# originalPSU48.net
KiCad netlist of a schematic drawn in Altium Designer
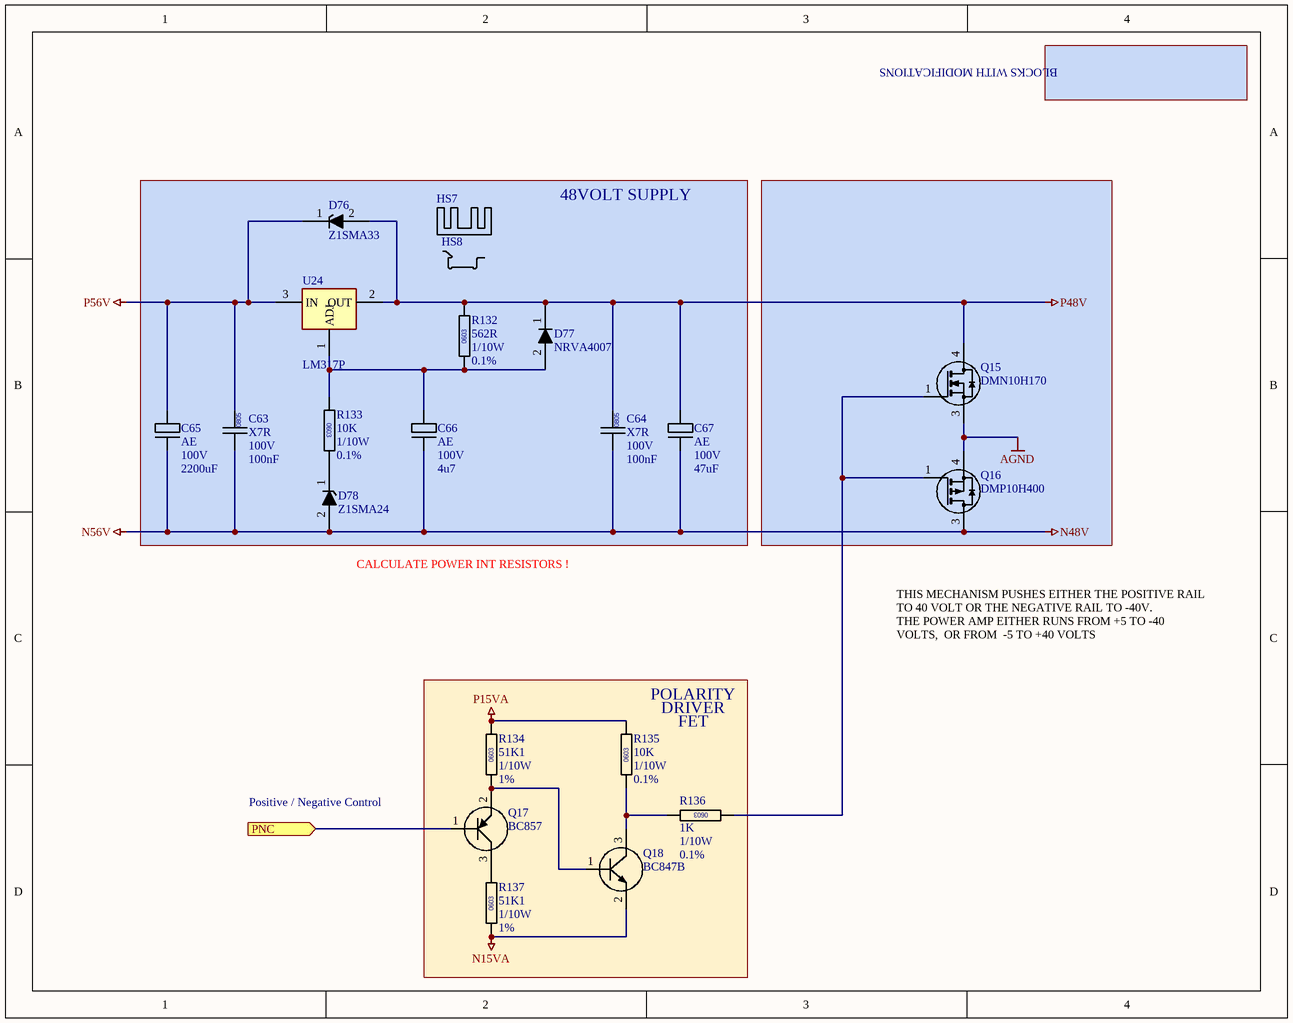
[diagram p0: originalPSU48.SchDoc]

(export (version "E")
  (design (tool "Eeschema 10.0.6"))
  (components
    (comp (ref "C63")
      (value "CAP0805")
      (footprint "CAPC0805")
      (description "CAPACITOR,CERAMIC,100nF,100V,X7R,0805")
      (fields
        (field (name "DIELECTRIC") "X7R")
        (field (name "VOLTAGE") "100V")
        (field (name "CAPACITANCE") "100nF")
      )
      (libsource (lib "CAPACITORS") (part "CAPC-0805-100nF-100V"))
    )
    (comp (ref "C64")
      (value "CAP0805")
      (footprint "CAPC0805")
      (description "CAPACITOR,CERAMIC,100nF,100V,X7R,0805")
      (fields
        (field (name "DIELECTRIC") "X7R")
        (field (name "VOLTAGE") "100V")
        (field (name "CAPACITANCE") "100nF")
      )
      (libsource (lib "CAPACITORS") (part "CAPC-0805-100nF-100V"))
    )
    (comp (ref "C65")
      (value "CAP0603")
      (footprint "CAPAE-NICHICON-LGY2A222MELC30")
      (description "CAPACITOR,ALU,2200uF,100V,TH,P10mm,D35mm,H32mm,SNAP")
      (fields
        (field (name "DIELECTRIC") "AE")
        (field (name "VOLTAGE") "100V")
        (field (name "CAPACITANCE") "2200uF")
      )
      (libsource (lib "CAPACITORS") (part "CAPP-AE-2200uF-100V-TH100P350D320H"))
    )
    (comp (ref "C66")
      (value "CAP0603")
      (footprint "CAPAE-PANASONIC-ECA-2AM4R7I")
      (description "CAPACITOR,ALU,4u7,100V,TH,P0.25mm,D50mm,H12mm")
      (fields
        (field (name "DIELECTRIC") "AE")
        (field (name "VOLTAGE") "100V")
        (field (name "CAPACITANCE") "4u7")
      )
      (libsource (lib "CAPACITORS") (part "CAPP-AE-4u7-100V-TH025P050D120H"))
    )
    (comp (ref "C67")
      (value "CAP0603")
      (footprint "CAPAE-KEMET-ESL476M100AH9AA")
      (description "CAPACITOR,ALU,47uF,100V,TH,P5mm,D10mm,H14mm")
      (fields
        (field (name "DIELECTRIC") "AE")
        (field (name "VOLTAGE") "100V")
        (field (name "CAPACITANCE") "47uF")
      )
      (libsource (lib "CAPACITORS") (part "CAPP-AE-47uF-100V-TH050P100D140H"))
    )
    (comp (ref "D76")
      (value "Z1SMA33")
      (footprint "DO214AC")
      (description "DIODE,ZENER,33V,1W,Z1SMA33,DO214AC(SMA)")
      (libsource (lib "DIODES") (part "ZENER-DIOTEC-Z1SMA33"))
    )
    (comp (ref "D77")
      (value "NRVA4007")
      (footprint "DO214AC")
      (description "DIODE,RECTIFIER,1000V,1A,ONSEMI,NRVA4007,SMA")
      (libsource (lib "DIODES") (part "DIODE-ONSEMI-NRVA4007T3G"))
    )
    (comp (ref "D78")
      (value "Z1SMA24")
      (footprint "DO214AC")
      (description "DIODE,ZENER,24V,1W,Z1SMA24,DO214AC(SMA)")
      (libsource (lib "DIODES") (part "ZENER-DIOTEC-Z1SMA24"))
    )
    (comp (ref "HS7")
      (value "HEATSINK-CUI-HSS06-C20-P32")
      (footprint "HEATSINK-CUI-HSS06-C20-P32")
      (description "HEATSINKSTAMPED,CLIP-ON,BOARDMOUNT,3W,25C/W,CUI,HSS06-C20-P32")
      (libsource (lib "HEATSINK") (part "HEATSINK-CUI-HSS06-C20-P32"))
    )
    (comp (ref "HS8")
      (value "HEATSINK-CUI-HSC-05")
      (footprint "HEATSINK-CUI-HSS06-C20-P32")
      (description "HEATSINK,CLIP FOR HSS01-B20-CP")
      (libsource (lib "HEATSINK") (part "HEATSINK-CUI-HSC-05"))
    )
    (comp (ref "Q15")
      (value "DMN10H170")
      (footprint "DPAK")
      (description "XSTR,NMOS,100V,12A,DMN10H170SK3-13,DPAK")
      (libsource (lib "TRANSISTORS") (part "XSTR-NMOS-DIODES-DMN10H170SK3-13"))
    )
    (comp (ref "Q16")
      (value "DMP10H400")
      (footprint "DPAK")
      (description "XSTR,PMOS,100V,5.6A,DMP10H400SK3-13,DPAK")
      (libsource (lib "TRANSISTORS") (part "XSTR-PMOS-DIODES-DMP10H400SK3-13"))
    )
    (comp (ref "Q17")
      (value "BC857")
      (footprint "SOT23")
      (description "XSTR,PNP,SOT23,BC857,SOT23")
      (libsource (lib "TRANSISTORS") (part "XSTR-PNP-BC857"))
    )
    (comp (ref "Q18")
      (value "BC847B")
      (footprint "SOT23")
      (description "XSTR,NPN,45V,0.1A,,BC847B,SOT23")
      (libsource (lib "TRANSISTORS") (part "XSTR-NPN-BC847"))
    )
    (comp (ref "R132")
      (value "562R")
      (footprint "RESC0603")
      (description "RESISTOR,562R,0.1%,100mW,0603 (1608)")
      (fields
        (field (name "POWER") "1/10W")
        (field (name "TOLERANCE") "0.1%")
        (field (name "Comment") "RESC0603")
      )
      (libsource (lib "RESISTORS") (part "RESC-0603-562R-0.1%-1/10W"))
    )
    (comp (ref "R133")
      (value "10K")
      (footprint "RESC0603")
      (description "RESISTOR,10K,0.1%,100mW,0603 (1608)")
      (fields
        (field (name "POWER") "1/10W")
        (field (name "TOLERANCE") "0.1%")
        (field (name "Comment") "RESC0603")
      )
      (libsource (lib "RESISTORS") (part "RESC-0603-10K-0.1%-1/10W"))
    )
    (comp (ref "R134")
      (value "51K1")
      (footprint "RESC0603")
      (description "RESISTOR,51K1,1%,100mW,0603 (1608)")
      (fields
        (field (name "POWER") "1/10W")
        (field (name "TOLERANCE") "1%")
        (field (name "Comment") "RESC0603")
      )
      (libsource (lib "RESISTORS") (part "RESC-0603-51K1-1%-1/10W"))
    )
    (comp (ref "R135")
      (value "10K")
      (footprint "RESC0603")
      (description "RESISTOR,10K,0.1%,100mW,0603 (1608)")
      (fields
        (field (name "POWER") "1/10W")
        (field (name "TOLERANCE") "0.1%")
        (field (name "Comment") "RESC0603")
      )
      (libsource (lib "RESISTORS") (part "RESC-0603-10K-0.1%-1/10W"))
    )
    (comp (ref "R136")
      (value "1K")
      (footprint "RESC0603")
      (description "RESISTOR,1K,0.1%,100mW,0603 (1608)")
      (fields
        (field (name "POWER") "1/10W")
        (field (name "TOLERANCE") "0.1%")
        (field (name "Comment") "RESC0603")
      )
      (libsource (lib "RESISTORS") (part "RESC-0603-1K-0.1%-1/10W"))
    )
    (comp (ref "R137")
      (value "51K1")
      (footprint "RESC0603")
      (description "RESISTOR,51K1,1%,100mW,0603 (1608)")
      (fields
        (field (name "POWER") "1/10W")
        (field (name "TOLERANCE") "1%")
        (field (name "Comment") "RESC0603")
      )
      (libsource (lib "RESISTORS") (part "RESC-0603-51K1-1%-1/10W"))
    )
    (comp (ref "U24")
      (value "LM317P")
      (footprint "TO220V-OVERMOLD")
      (description "IC,VOLTAGE REG,LIN,POSITIVE,ADJ,LM317P,TO220")
      (libsource (lib "IC-REG") (part "IC-ST-LM317P-TO220FP"))
    )
  )
  (nets
    (net (code "1") (name "/PNC") (class "Default")
      (node (ref "Q17") (pin "1") (pinfunction "B_1") (pintype "passive"))
    )
    (net (code "2") (name "AGND") (class "Default")
      (node (ref "Q15") (pin "3") (pinfunction "S_3") (pintype "passive"))
      (node (ref "Q16") (pin "4") (pinfunction "S_4") (pintype "passive"))
    )
    (net (code "3") (name "N15VA") (class "Default")
      (node (ref "Q18") (pin "2") (pinfunction "E_2") (pintype "passive"))
      (node (ref "R137") (pin "2") (pintype "passive"))
    )
    (net (code "4") (name "N48V") (class "Default")
      (node (ref "C63") (pin "2") (pintype "passive"))
      (node (ref "C64") (pin "2") (pintype "passive"))
      (node (ref "C65") (pin "2") (pintype "passive"))
      (node (ref "C66") (pin "2") (pintype "passive"))
      (node (ref "C67") (pin "2") (pintype "passive"))
      (node (ref "D78") (pin "2") (pinfunction "A_2") (pintype "passive"))
      (node (ref "Q16") (pin "3") (pinfunction "D_3") (pintype "passive"))
    )
    (net (code "5") (name "Net-(D77-A)") (class "Default")
      (node (ref "C66") (pin "1") (pintype "passive"))
      (node (ref "D77") (pin "2") (pinfunction "A_2") (pintype "passive"))
      (node (ref "R132") (pin "2") (pintype "passive"))
      (node (ref "R133") (pin "2") (pintype "passive"))
      (node (ref "U24") (pin "1") (pinfunction "ADJ_1") (pintype "passive"))
    )
    (net (code "6") (name "Net-(D78-K)") (class "Default")
      (node (ref "D78") (pin "1") (pinfunction "K_1") (pintype "passive"))
      (node (ref "R133") (pin "1") (pintype "passive"))
    )
    (net (code "7") (name "Net-(Q15-G1)") (class "Default")
      (node (ref "Q15") (pin "1") (pinfunction "G1_1") (pintype "passive"))
      (node (ref "Q16") (pin "1") (pinfunction "G1_1") (pintype "passive"))
      (node (ref "R136") (pin "2") (pintype "passive"))
    )
    (net (code "8") (name "Net-(Q17-C)") (class "Default")
      (node (ref "Q17") (pin "3") (pinfunction "C_3") (pintype "passive"))
      (node (ref "R137") (pin "1") (pintype "passive"))
    )
    (net (code "9") (name "Net-(Q17-E)") (class "Default")
      (node (ref "Q17") (pin "2") (pinfunction "E_2") (pintype "passive"))
      (node (ref "Q18") (pin "1") (pinfunction "B_1") (pintype "passive"))
      (node (ref "R134") (pin "2") (pintype "passive"))
    )
    (net (code "10") (name "Net-(Q18-C)") (class "Default")
      (node (ref "Q18") (pin "3") (pinfunction "C_3") (pintype "passive"))
      (node (ref "R135") (pin "2") (pintype "passive"))
      (node (ref "R136") (pin "1") (pintype "passive"))
    )
    (net (code "11") (name "P15VA") (class "Default")
      (node (ref "R134") (pin "1") (pintype "passive"))
      (node (ref "R135") (pin "1") (pintype "passive"))
    )
    (net (code "12") (name "P48V") (class "Default")
      (node (ref "C64") (pin "1") (pintype "passive"))
      (node (ref "C67") (pin "1") (pintype "passive"))
      (node (ref "D76") (pin "2") (pinfunction "A_2") (pintype "passive"))
      (node (ref "D77") (pin "1") (pinfunction "K_1") (pintype "passive"))
      (node (ref "Q15") (pin "4") (pinfunction "D_4") (pintype "passive"))
      (node (ref "R132") (pin "1") (pintype "passive"))
      (node (ref "U24") (pin "2") (pinfunction "OUT_2") (pintype "passive"))
    )
    (net (code "13") (name "P56V") (class "Default")
      (node (ref "C63") (pin "1") (pintype "passive"))
      (node (ref "C65") (pin "1") (pintype "passive"))
      (node (ref "D76") (pin "1") (pinfunction "K_1") (pintype "passive"))
      (node (ref "U24") (pin "3") (pinfunction "IN_3") (pintype "passive"))
    )
  )
)
